# Wifi_Modem_PET-Adapter.net
KiCad netlist of a schematic drawn in EAGLE
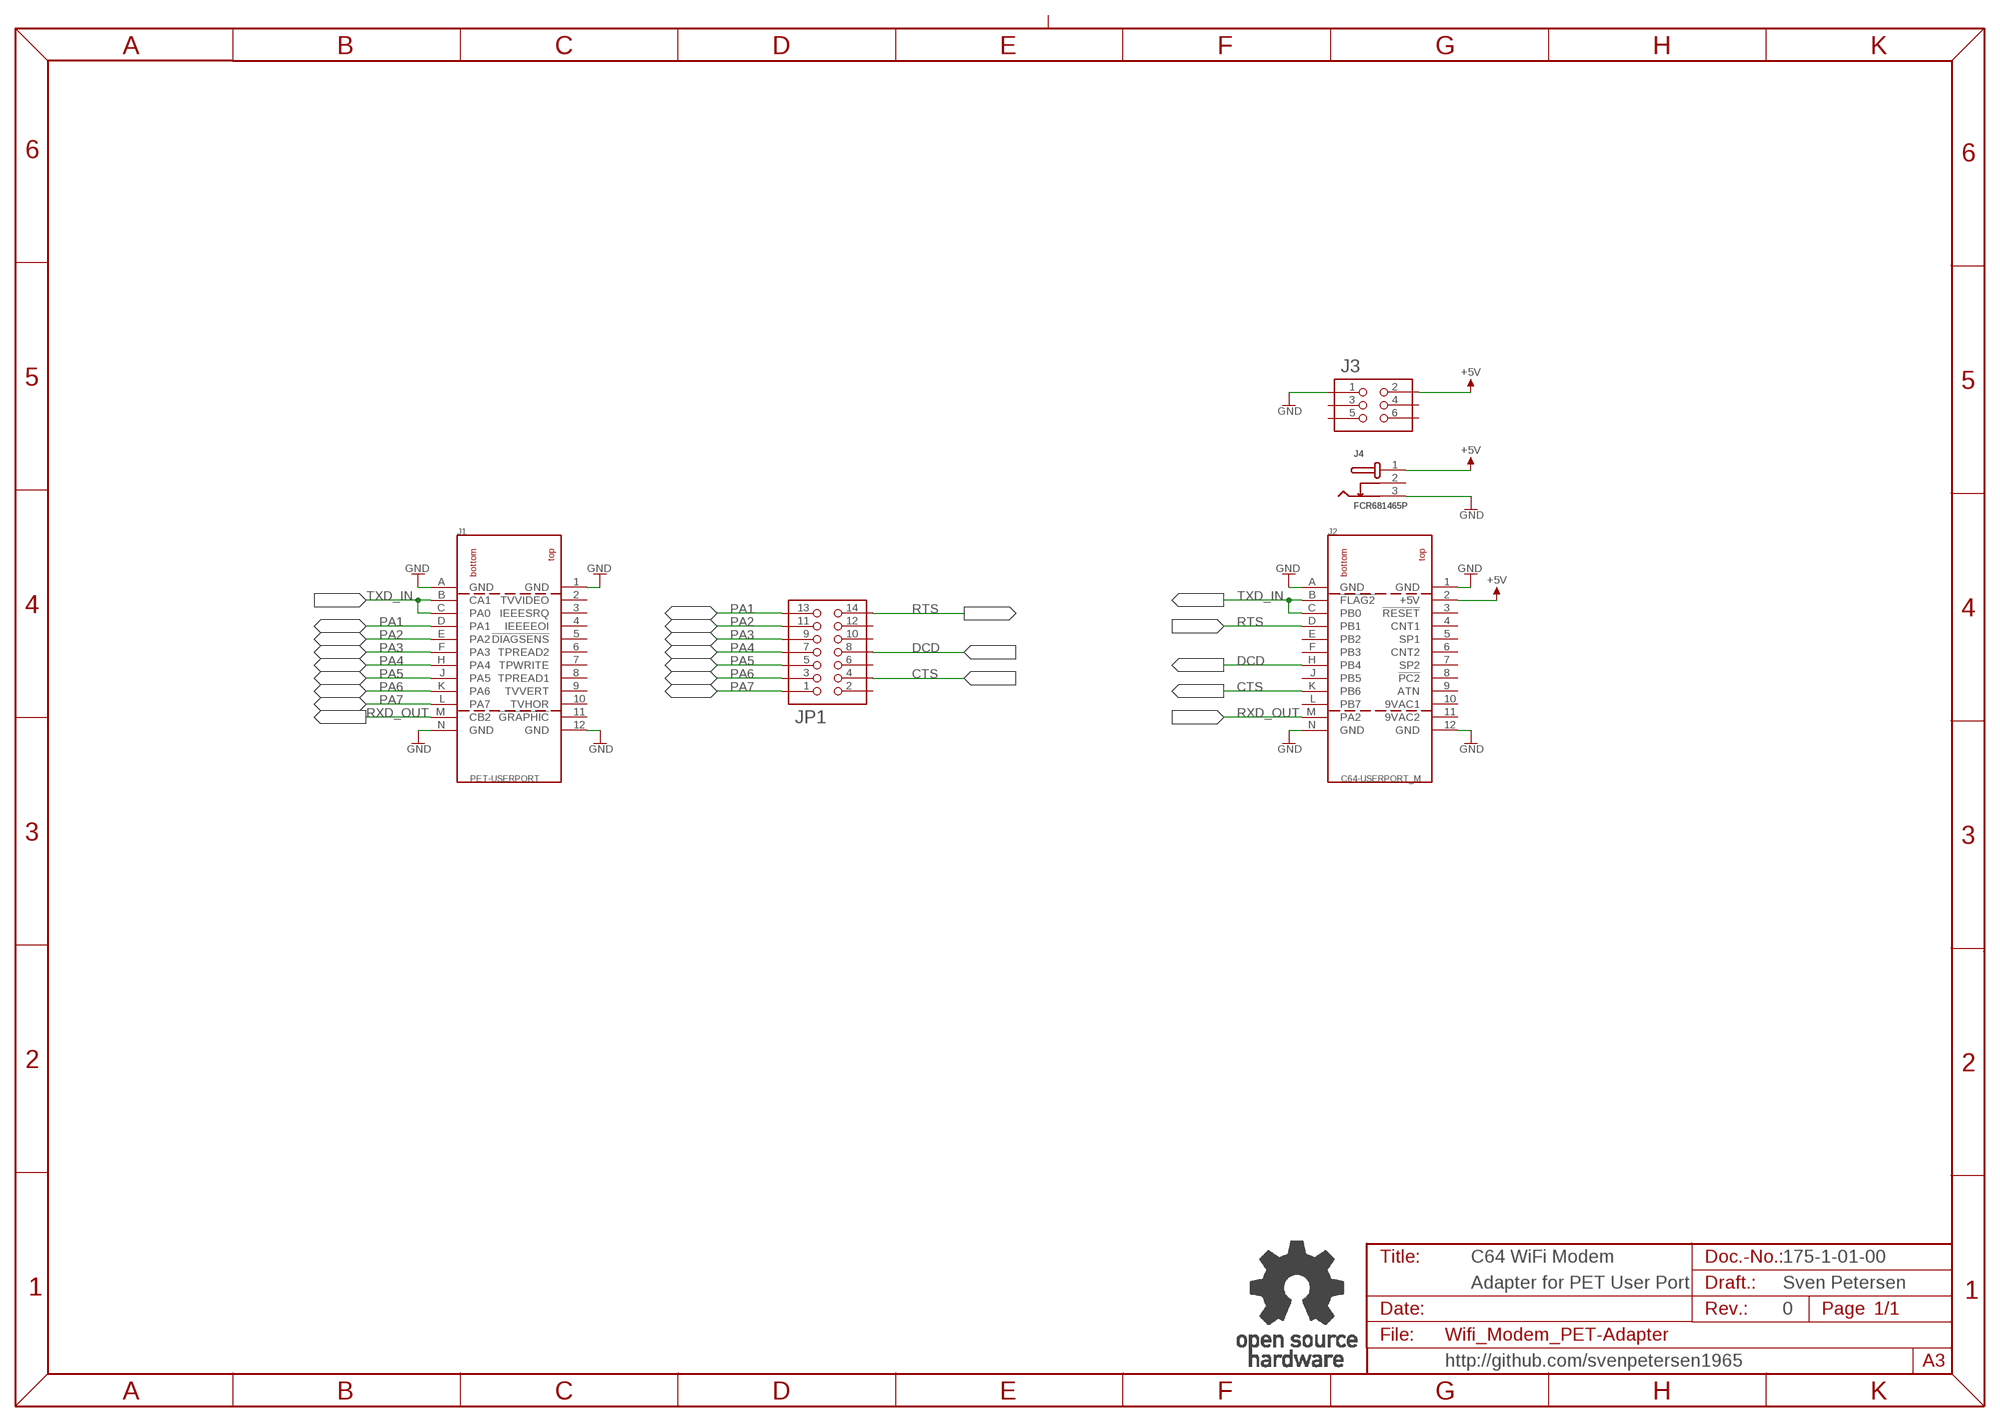
[diagram p0: schematic, sheet 1]

(export (version "E")
  (design (tool "Eeschema 10.0.6"))
  (components
    (comp (ref "J1")
      (value "PET-USERPORT")
      (footprint "eagle-import:USERPORT")
      (libsource (lib "eagle-import") (part "PET-USERPORT"))
    )
    (comp (ref "J2")
      (value "C64-USERPORT_M")
      (footprint "eagle-import:USERPORT_M")
      (libsource (lib "eagle-import") (part "C64-USERPORT_M"))
    )
    (comp (ref "J3")
      (value "2X03WV")
      (footprint "eagle-import:2X03WV")
      (libsource (lib "eagle-import") (part "2X03WV"))
    )
    (comp (ref "J4")
      (value "FCR681465P")
      (footprint "eagle-import:FCR681465P")
      (libsource (lib "eagle-import") (part "FCR681465P"))
    )
    (comp (ref "JP1")
      (value "PINHD-2X7")
      (footprint "eagle-import:2X07")
      (libsource (lib "eagle-import") (part "PINHD-2X7"))
    )
    (comp (ref "U$2")
      (value "OPEN_SOURCE_HW")
      (footprint "eagle-import:OPENHW")
      (libsource (lib "eagle-import") (part "OPEN_SOURCE_HW"))
    )
  )
  (nets
    (net (code "1") (name "+5V") (class "Default")
      (node (ref "J2") (pin "2") (pinfunction "+5V_2") (pintype "power_in"))
      (node (ref "J3") (pin "2") (pinfunction "2_2") (pintype "passive"))
      (node (ref "J4") (pin "1") (pinfunction "1_1") (pintype "bidirectional"))
    )
    (net (code "2") (name "/9VAC1") (class "Default")
      (node (ref "J2") (pin "10") (pinfunction "9VAC1_10") (pintype "power_in"))
    )
    (net (code "3") (name "/9VAC2") (class "Default")
      (node (ref "J2") (pin "11") (pinfunction "9VAC2_11") (pintype "power_in"))
    )
    (net (code "4") (name "/CTS") (class "Default")
      (node (ref "J2") (pin "K") (pinfunction "PB6_K") (pintype "bidirectional"))
      (node (ref "JP1") (pin "4") (pinfunction "4_4") (pintype "passive"))
    )
    (net (code "5") (name "/DCD") (class "Default")
      (node (ref "J2") (pin "H") (pinfunction "PB4_H") (pintype "bidirectional"))
      (node (ref "JP1") (pin "8") (pinfunction "8_8") (pintype "passive"))
    )
    (net (code "6") (name "/PA1") (class "Default")
      (node (ref "J1") (pin "D") (pinfunction "PA1_D") (pintype "bidirectional"))
      (node (ref "JP1") (pin "13") (pinfunction "13_13") (pintype "passive"))
    )
    (net (code "7") (name "/PA2") (class "Default")
      (node (ref "J1") (pin "E") (pinfunction "PA2_E") (pintype "bidirectional"))
      (node (ref "JP1") (pin "11") (pinfunction "11_11") (pintype "passive"))
    )
    (net (code "8") (name "/PA3") (class "Default")
      (node (ref "J1") (pin "F") (pinfunction "PA3_F") (pintype "bidirectional"))
      (node (ref "JP1") (pin "9") (pinfunction "9_9") (pintype "passive"))
    )
    (net (code "9") (name "/PA4") (class "Default")
      (node (ref "J1") (pin "H") (pinfunction "PA4_H") (pintype "bidirectional"))
      (node (ref "JP1") (pin "7") (pinfunction "7_7") (pintype "passive"))
    )
    (net (code "10") (name "/PA5") (class "Default")
      (node (ref "J1") (pin "J") (pinfunction "PA5_J") (pintype "bidirectional"))
      (node (ref "JP1") (pin "5") (pinfunction "5_5") (pintype "passive"))
    )
    (net (code "11") (name "/PA6") (class "Default")
      (node (ref "J1") (pin "K") (pinfunction "PA6_K") (pintype "bidirectional"))
      (node (ref "JP1") (pin "3") (pinfunction "3_3") (pintype "passive"))
    )
    (net (code "12") (name "/PA7") (class "Default")
      (node (ref "J1") (pin "L") (pinfunction "PA7_L") (pintype "bidirectional"))
      (node (ref "JP1") (pin "1") (pinfunction "1_1") (pintype "passive"))
    )
    (net (code "13") (name "/RTS") (class "Default")
      (node (ref "J2") (pin "D") (pinfunction "PB1_D") (pintype "bidirectional"))
      (node (ref "JP1") (pin "14") (pinfunction "14_14") (pintype "passive"))
    )
    (net (code "14") (name "/RXD_OUT") (class "Default")
      (node (ref "J1") (pin "M") (pinfunction "CB2_M") (pintype "bidirectional"))
      (node (ref "J2") (pin "M") (pinfunction "PA2_M") (pintype "bidirectional"))
    )
    (net (code "15") (name "/TXD_IN") (class "Default")
      (node (ref "J1") (pin "B") (pinfunction "CA1_B") (pintype "input"))
      (node (ref "J1") (pin "C") (pinfunction "PA0_C") (pintype "bidirectional"))
      (node (ref "J2") (pin "B") (pinfunction "~{FLAG2}_B") (pintype "input"))
      (node (ref "J2") (pin "C") (pinfunction "PB0_C") (pintype "bidirectional"))
    )
    (net (code "16") (name "GND") (class "Default")
      (node (ref "J1") (pin "1") (pinfunction "GND_1") (pintype "power_in"))
      (node (ref "J1") (pin "12") (pinfunction "GND_12") (pintype "power_in"))
      (node (ref "J1") (pin "A") (pinfunction "GND_A") (pintype "power_in"))
      (node (ref "J1") (pin "N") (pinfunction "GND_N") (pintype "power_in"))
      (node (ref "J2") (pin "1") (pinfunction "GND_1") (pintype "power_in"))
      (node (ref "J2") (pin "12") (pinfunction "GND_12") (pintype "power_in"))
      (node (ref "J2") (pin "A") (pinfunction "GND_A") (pintype "power_in"))
      (node (ref "J2") (pin "N") (pinfunction "GND_N") (pintype "power_in"))
      (node (ref "J3") (pin "1") (pinfunction "1_1") (pintype "passive"))
      (node (ref "J4") (pin "3") (pinfunction "3_3") (pintype "bidirectional"))
    )
    (net (code "17") (name "unconnected-(J1-IEEEEOI-Pad4)") (class "Default")
      (node (ref "J1") (pin "4") (pinfunction "IEEEEOI_4") (pintype "output"))
    )
    (net (code "18") (name "unconnected-(J1-IEEESRQ-Pad3)") (class "Default")
      (node (ref "J1") (pin "3") (pinfunction "IEEESRQ_3") (pintype "output"))
    )
    (net (code "19") (name "unconnected-(J1-TPREAD1-Pad8)") (class "Default")
      (node (ref "J1") (pin "8") (pinfunction "TPREAD1_8") (pintype "output"))
    )
    (net (code "20") (name "unconnected-(J1-TPREAD2-Pad6)") (class "Default")
      (node (ref "J1") (pin "6") (pinfunction "TPREAD2_6") (pintype "output"))
    )
    (net (code "21") (name "unconnected-(J1-TPWRITE-Pad7)") (class "Default")
      (node (ref "J1") (pin "7") (pinfunction "TPWRITE_7") (pintype "output"))
    )
    (net (code "22") (name "unconnected-(J1-TVHOR-Pad10)") (class "Default")
      (node (ref "J1") (pin "10") (pinfunction "TVHOR_10") (pintype "output"))
    )
    (net (code "23") (name "unconnected-(J1-TVVERT-Pad9)") (class "Default")
      (node (ref "J1") (pin "9") (pinfunction "TVVERT_9") (pintype "output"))
    )
    (net (code "24") (name "unconnected-(J1-TVVIDEO-Pad2)") (class "Default")
      (node (ref "J1") (pin "2") (pinfunction "TVVIDEO_2") (pintype "output"))
    )
    (net (code "25") (name "unconnected-(J1-~{DIAGSENS}-Pad5)") (class "Default")
      (node (ref "J1") (pin "5") (pinfunction "~{DIAGSENS}_5") (pintype "output"))
    )
    (net (code "26") (name "unconnected-(J1-~{GRAPHIC}-Pad11)") (class "Default")
      (node (ref "J1") (pin "11") (pinfunction "~{GRAPHIC}_11") (pintype "output"))
    )
    (net (code "27") (name "unconnected-(J2-ATN-Pad9)") (class "Default")
      (node (ref "J2") (pin "9") (pinfunction "ATN_9") (pintype "bidirectional"))
    )
    (net (code "28") (name "unconnected-(J2-CNT1-Pad4)") (class "Default")
      (node (ref "J2") (pin "4") (pinfunction "CNT1_4") (pintype "input"))
    )
    (net (code "29") (name "unconnected-(J2-CNT2-Pad6)") (class "Default")
      (node (ref "J2") (pin "6") (pinfunction "CNT2_6") (pintype "input"))
    )
    (net (code "30") (name "unconnected-(J2-PB2-PadE)") (class "Default")
      (node (ref "J2") (pin "E") (pinfunction "PB2_E") (pintype "bidirectional"))
    )
    (net (code "31") (name "unconnected-(J2-PB3-PadF)") (class "Default")
      (node (ref "J2") (pin "F") (pinfunction "PB3_F") (pintype "bidirectional"))
    )
    (net (code "32") (name "unconnected-(J2-PB5-PadJ)") (class "Default")
      (node (ref "J2") (pin "J") (pinfunction "PB5_J") (pintype "bidirectional"))
    )
    (net (code "33") (name "unconnected-(J2-PB7-PadL)") (class "Default")
      (node (ref "J2") (pin "L") (pinfunction "PB7_L") (pintype "bidirectional"))
    )
    (net (code "34") (name "unconnected-(J2-SP1-Pad5)") (class "Default")
      (node (ref "J2") (pin "5") (pinfunction "SP1_5") (pintype "bidirectional"))
    )
    (net (code "35") (name "unconnected-(J2-SP2-Pad7)") (class "Default")
      (node (ref "J2") (pin "7") (pinfunction "SP2_7") (pintype "bidirectional"))
    )
    (net (code "36") (name "unconnected-(J2-~{PC2}-Pad8)") (class "Default")
      (node (ref "J2") (pin "8") (pinfunction "~{PC2}_8") (pintype "bidirectional"))
    )
    (net (code "37") (name "unconnected-(J2-~{RESET}-Pad3)") (class "Default")
      (node (ref "J2") (pin "3") (pinfunction "~{RESET}_3") (pintype "bidirectional"))
    )
    (net (code "38") (name "unconnected-(J3-Pad3)") (class "Default")
      (node (ref "J3") (pin "3") (pinfunction "3_3") (pintype "passive"))
    )
    (net (code "39") (name "unconnected-(J3-Pad4)") (class "Default")
      (node (ref "J3") (pin "4") (pinfunction "4_4") (pintype "passive"))
    )
    (net (code "40") (name "unconnected-(J3-Pad5)") (class "Default")
      (node (ref "J3") (pin "5") (pinfunction "5_5") (pintype "passive"))
    )
    (net (code "41") (name "unconnected-(J3-Pad6)") (class "Default")
      (node (ref "J3") (pin "6") (pinfunction "6_6") (pintype "passive"))
    )
    (net (code "42") (name "unconnected-(J4-Pad2)") (class "Default")
      (node (ref "J4") (pin "2") (pinfunction "2_2") (pintype "bidirectional"))
    )
    (net (code "43") (name "unconnected-(JP1-Pad2)") (class "Default")
      (node (ref "JP1") (pin "2") (pinfunction "2_2") (pintype "passive"))
    )
    (net (code "44") (name "unconnected-(JP1-Pad6)") (class "Default")
      (node (ref "JP1") (pin "6") (pinfunction "6_6") (pintype "passive"))
    )
    (net (code "45") (name "unconnected-(JP1-Pad10)") (class "Default")
      (node (ref "JP1") (pin "10") (pinfunction "10_10") (pintype "passive"))
    )
    (net (code "46") (name "unconnected-(JP1-Pad12)") (class "Default")
      (node (ref "JP1") (pin "12") (pinfunction "12_12") (pintype "passive"))
    )
  )
)
